# Right_Ear_Board.net
KiCad netlist of a schematic drawn in EAGLE
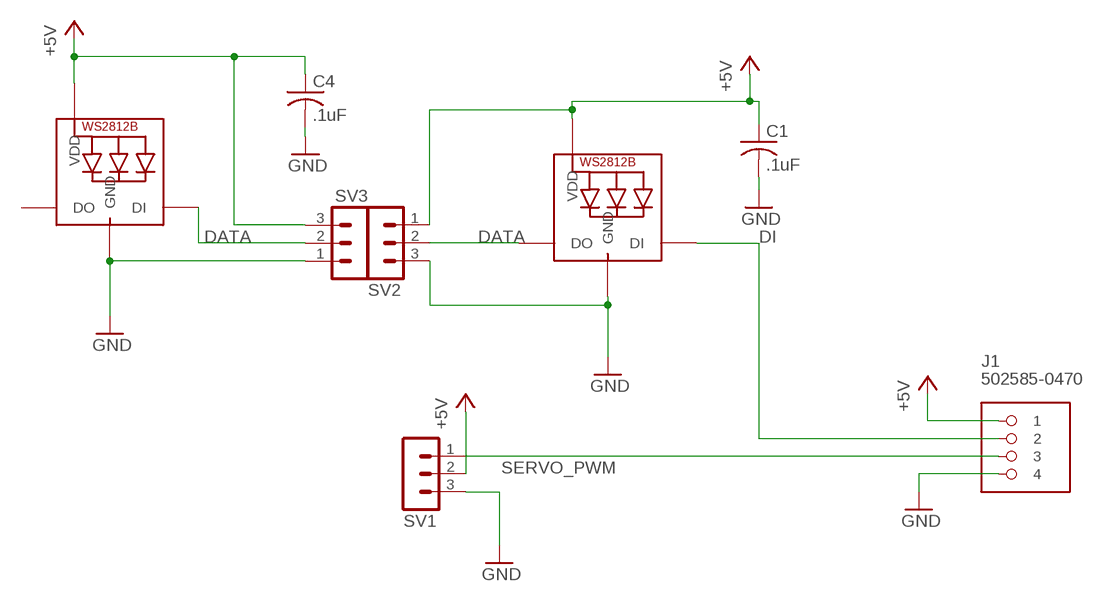
[diagram p0: schematic, sheet 1]

(export (version "E")
  (design (tool "Eeschema 10.0.6"))
  (components
    (comp (ref "C1")
      (value ".1uF")
      (footprint "eagle-import:C0603K")
      (fields (field (name "PARTNO") "GRM188R61A106KE69D"))
      (libsource (lib "eagle-import") (part "C-USC0603K"))
    )
    (comp (ref "C4")
      (value ".1uF")
      (footprint "eagle-import:C0603K")
      (fields (field (name "PARTNO") "GRM188R61A106KE69D"))
      (libsource (lib "eagle-import") (part "C-USC0603K"))
    )
    (comp (ref "J1")
      (value "502585-0470")
      (footprint "eagle-import:MOLEX-CLIKMATE-4-R_A")
      (libsource (lib "eagle-import") (part "MOLEX_CLICKMATE-4-R/A"))
    )
    (comp (ref "LED1")
      (value "WS2812B5050")
      (footprint "eagle-import:WS2812B")
      (libsource (lib "eagle-import") (part "WS2812B5050"))
    )
    (comp (ref "LED7")
      (value "WS2812B5050")
      (footprint "eagle-import:WS2812B")
      (libsource (lib "eagle-import") (part "WS2812B5050"))
    )
    (comp (ref "SV1")
      (value "MA03-1")
      (footprint "eagle-import:MA03-1")
      (libsource (lib "eagle-import") (part "MA03-1"))
    )
    (comp (ref "SV2")
      (value "MA03-1")
      (footprint "eagle-import:MA03-1")
      (libsource (lib "eagle-import") (part "MA03-1"))
    )
    (comp (ref "SV3")
      (value "MA03-1")
      (footprint "eagle-import:MA03-1")
      (libsource (lib "eagle-import") (part "MA03-1"))
    )
  )
  (nets
    (net (code "1") (name "+5V") (class "Default")
      (node (ref "C1") (pin "1") (pinfunction "1_1") (pintype "passive"))
      (node (ref "C4") (pin "1") (pinfunction "1_1") (pintype "passive"))
      (node (ref "J1") (pin "1") (pinfunction "1_1") (pintype "bidirectional"))
      (node (ref "LED1") (pin "1-VDD") (pinfunction "VDD_1-VDD") (pintype "power_in"))
      (node (ref "LED7") (pin "1-VDD") (pinfunction "VDD_1-VDD") (pintype "power_in"))
      (node (ref "SV1") (pin "2") (pinfunction "2_2") (pintype "passive"))
      (node (ref "SV2") (pin "1") (pinfunction "1_1") (pintype "passive"))
      (node (ref "SV3") (pin "3") (pinfunction "3_3") (pintype "passive"))
    )
    (net (code "2") (name "/DATA") (class "Default")
      (node (ref "LED1") (pin "2-DOUT") (pinfunction "DO_2-DOUT") (pintype "output"))
      (node (ref "LED7") (pin "4-DIN") (pinfunction "DI_4-DIN") (pintype "input"))
      (node (ref "SV2") (pin "2") (pinfunction "2_2") (pintype "passive"))
      (node (ref "SV3") (pin "2") (pinfunction "2_2") (pintype "passive"))
    )
    (net (code "3") (name "/DI") (class "Default")
      (node (ref "J1") (pin "2") (pinfunction "2_2") (pintype "bidirectional"))
      (node (ref "LED1") (pin "4-DIN") (pinfunction "DI_4-DIN") (pintype "input"))
    )
    (net (code "4") (name "/SERVO_PWM") (class "Default")
      (node (ref "J1") (pin "3") (pinfunction "3_3") (pintype "bidirectional"))
      (node (ref "SV1") (pin "1") (pinfunction "1_1") (pintype "passive"))
    )
    (net (code "5") (name "GND") (class "Default")
      (node (ref "C1") (pin "2") (pinfunction "2_2") (pintype "passive"))
      (node (ref "C4") (pin "2") (pinfunction "2_2") (pintype "passive"))
      (node (ref "J1") (pin "4") (pinfunction "4_4") (pintype "bidirectional"))
      (node (ref "LED1") (pin "3-GND") (pinfunction "GND_3-GND") (pintype "power_in"))
      (node (ref "LED7") (pin "3-GND") (pinfunction "GND_3-GND") (pintype "power_in"))
      (node (ref "SV1") (pin "3") (pinfunction "3_3") (pintype "passive"))
      (node (ref "SV2") (pin "3") (pinfunction "3_3") (pintype "passive"))
      (node (ref "SV3") (pin "1") (pinfunction "1_1") (pintype "passive"))
    )
    (net (code "6") (name "unconnected-(LED7-DO-Pad2-DOUT)") (class "Default")
      (node (ref "LED7") (pin "2-DOUT") (pinfunction "DO_2-DOUT") (pintype "output"))
    )
  )
)
